# Schematic_MON-14.net
KiCad netlist of a schematic drawn in EAGLE
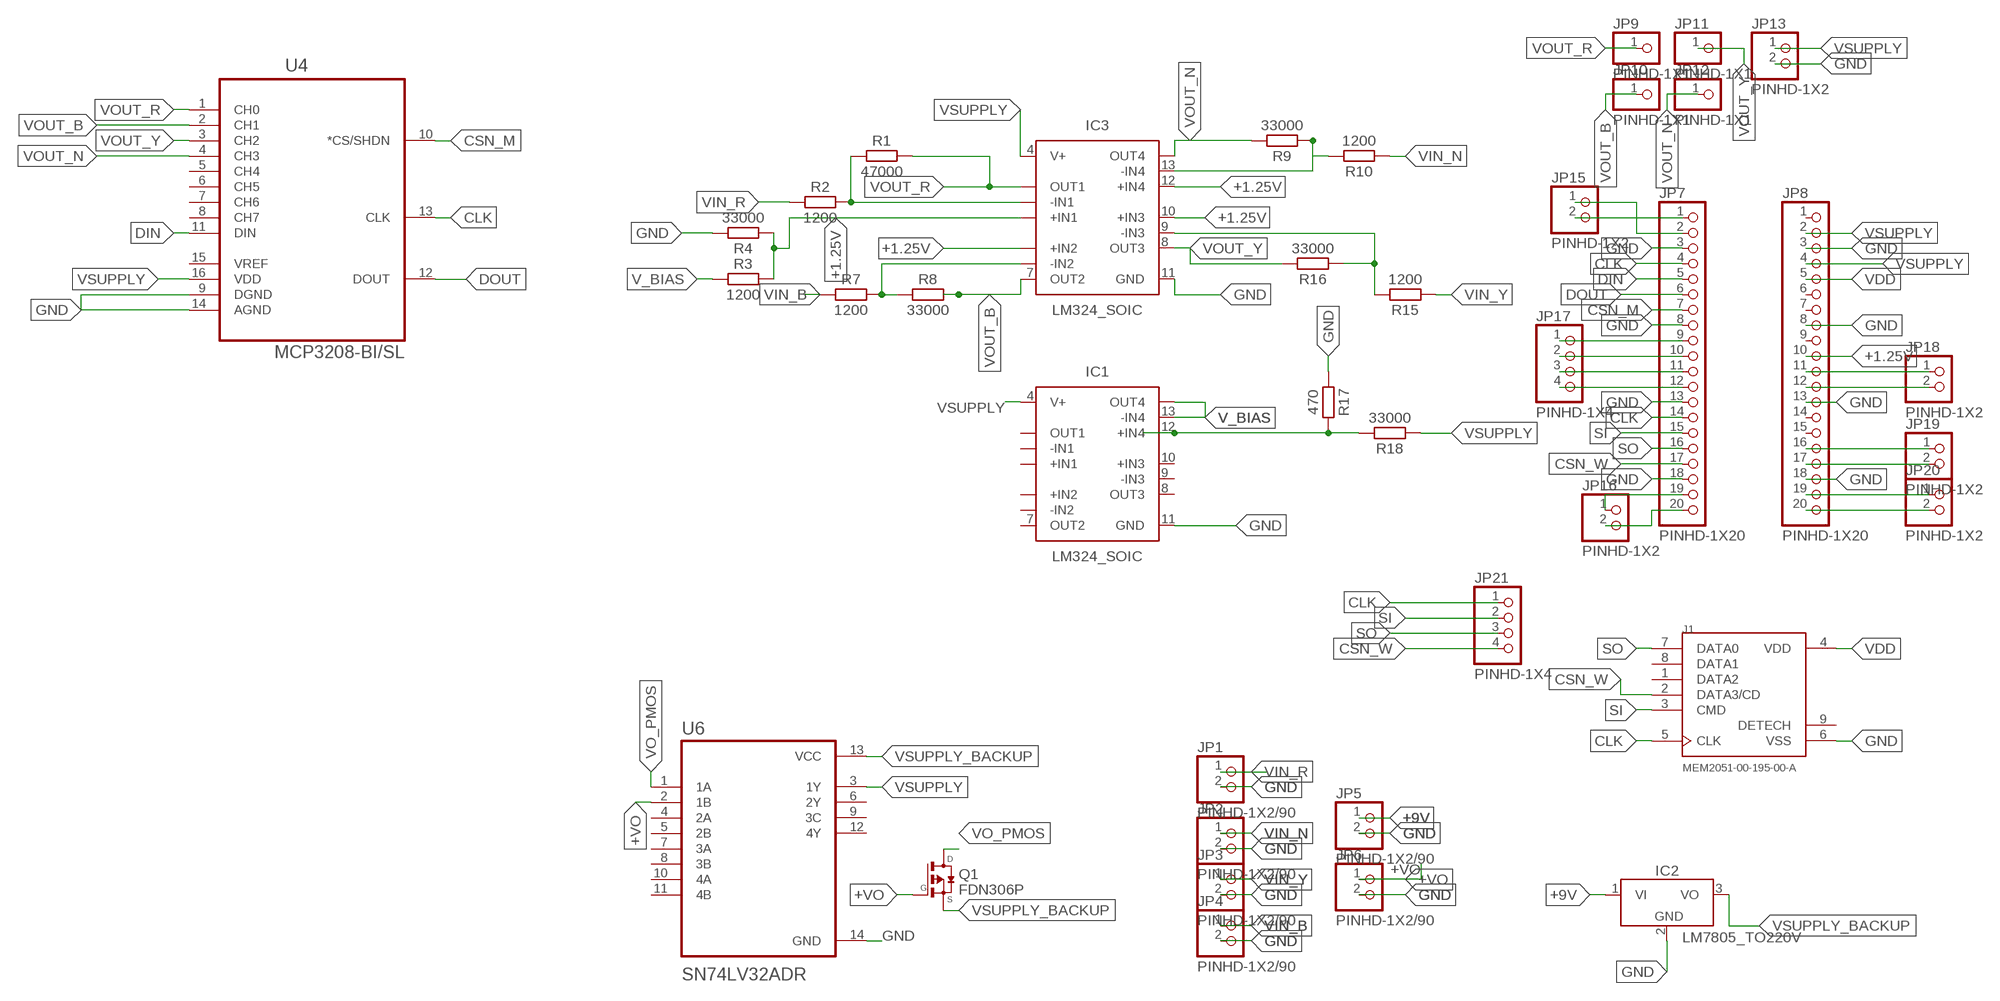
[diagram p0: schematic, sheet 1]

(export (version "E")
  (design (tool "Eeschema 10.0.6"))
  (components
    (comp (ref "IC1")
      (value "LM324_SOIC")
      (footprint "eagle-import:SOIC127P600X175-14N")
      (fields (field (name "MANUFACTURER") "Generic"))
      (libsource (lib "eagle-import") (part "LM324_SOIC"))
    )
    (comp (ref "IC2")
      (value "LM7805_TO220V")
      (footprint "eagle-import:TO220V")
      (fields (field (name "MANUFACTURER") "Generic"))
      (libsource (lib "eagle-import") (part "LM7805_TO220V"))
    )
    (comp (ref "IC3")
      (value "LM324_SOIC")
      (footprint "eagle-import:SOIC127P600X175-14N")
      (fields (field (name "MANUFACTURER") "Generic"))
      (libsource (lib "eagle-import") (part "LM324_SOIC"))
    )
    (comp (ref "J1")
      (value "MEM2051-00-195-00-A")
      (footprint "eagle-import:GCT_MEM2051-00-195-00-A")
      (fields (field (name "MANUFACTURER") "GCT"))
      (libsource (lib "eagle-import") (part "MEM2051-00-195-00-A"))
    )
    (comp (ref "JP1")
      (value "PINHD-1X2/90")
      (footprint "eagle-import:1X02_90")
      (libsource (lib "eagle-import") (part "PINHD-1X2/90"))
    )
    (comp (ref "JP2")
      (value "PINHD-1X2/90")
      (footprint "eagle-import:1X02_90")
      (libsource (lib "eagle-import") (part "PINHD-1X2/90"))
    )
    (comp (ref "JP3")
      (value "PINHD-1X2/90")
      (footprint "eagle-import:1X02_90")
      (libsource (lib "eagle-import") (part "PINHD-1X2/90"))
    )
    (comp (ref "JP4")
      (value "PINHD-1X2/90")
      (footprint "eagle-import:1X02_90")
      (libsource (lib "eagle-import") (part "PINHD-1X2/90"))
    )
    (comp (ref "JP5")
      (value "PINHD-1X2/90")
      (footprint "eagle-import:1X02_90")
      (libsource (lib "eagle-import") (part "PINHD-1X2/90"))
    )
    (comp (ref "JP6")
      (value "PINHD-1X2/90")
      (footprint "eagle-import:1X02_90")
      (libsource (lib "eagle-import") (part "PINHD-1X2/90"))
    )
    (comp (ref "JP7")
      (value "PINHD-1X20")
      (footprint "eagle-import:1X20")
      (libsource (lib "eagle-import") (part "PINHD-1X20"))
    )
    (comp (ref "JP8")
      (value "PINHD-1X20")
      (footprint "eagle-import:1X20")
      (libsource (lib "eagle-import") (part "PINHD-1X20"))
    )
    (comp (ref "JP9")
      (value "PINHD-1X1")
      (footprint "eagle-import:1X01")
      (libsource (lib "eagle-import") (part "PINHD-1X1"))
    )
    (comp (ref "JP10")
      (value "PINHD-1X1")
      (footprint "eagle-import:1X01")
      (libsource (lib "eagle-import") (part "PINHD-1X1"))
    )
    (comp (ref "JP11")
      (value "PINHD-1X1")
      (footprint "eagle-import:1X01")
      (libsource (lib "eagle-import") (part "PINHD-1X1"))
    )
    (comp (ref "JP12")
      (value "PINHD-1X1")
      (footprint "eagle-import:1X01")
      (libsource (lib "eagle-import") (part "PINHD-1X1"))
    )
    (comp (ref "JP13")
      (value "PINHD-1X2")
      (footprint "eagle-import:1X02")
      (libsource (lib "eagle-import") (part "PINHD-1X2"))
    )
    (comp (ref "JP15")
      (value "PINHD-1X2")
      (footprint "eagle-import:1X02")
      (libsource (lib "eagle-import") (part "PINHD-1X2"))
    )
    (comp (ref "JP16")
      (value "PINHD-1X2")
      (footprint "eagle-import:1X02")
      (libsource (lib "eagle-import") (part "PINHD-1X2"))
    )
    (comp (ref "JP17")
      (value "PINHD-1X4")
      (footprint "eagle-import:1X04")
      (libsource (lib "eagle-import") (part "PINHD-1X4"))
    )
    (comp (ref "JP18")
      (value "PINHD-1X2")
      (footprint "eagle-import:1X02")
      (libsource (lib "eagle-import") (part "PINHD-1X2"))
    )
    (comp (ref "JP19")
      (value "PINHD-1X2")
      (footprint "eagle-import:1X02")
      (libsource (lib "eagle-import") (part "PINHD-1X2"))
    )
    (comp (ref "JP20")
      (value "PINHD-1X2")
      (footprint "eagle-import:1X02")
      (libsource (lib "eagle-import") (part "PINHD-1X2"))
    )
    (comp (ref "JP21")
      (value "PINHD-1X4")
      (footprint "eagle-import:1X04")
      (libsource (lib "eagle-import") (part "PINHD-1X4"))
    )
    (comp (ref "Q1")
      (value "FDN306P")
      (footprint "eagle-import:SSOT-3")
      (libsource (lib "eagle-import") (part "FDN306P"))
    )
    (comp (ref "R1")
      (value "47000")
      (footprint "eagle-import:RESC3216X70")
      (libsource (lib "eagle-import") (part "RCHIP-1206(3216-METRIC)_"))
    )
    (comp (ref "R2")
      (value "1200")
      (footprint "eagle-import:RESC3216X70")
      (libsource (lib "eagle-import") (part "RCHIP-1206(3216-METRIC)_"))
    )
    (comp (ref "R3")
      (value "1200")
      (footprint "eagle-import:RESC3216X70")
      (libsource (lib "eagle-import") (part "RCHIP-1206(3216-METRIC)_"))
    )
    (comp (ref "R4")
      (value "33000")
      (footprint "eagle-import:RESC3216X70")
      (libsource (lib "eagle-import") (part "RCHIP-1206(3216-METRIC)_"))
    )
    (comp (ref "R7")
      (value "1200")
      (footprint "eagle-import:RESC3216X70")
      (libsource (lib "eagle-import") (part "RCHIP-1206(3216-METRIC)_"))
    )
    (comp (ref "R8")
      (value "33000")
      (footprint "eagle-import:RESC3216X70")
      (libsource (lib "eagle-import") (part "RCHIP-1206(3216-METRIC)_"))
    )
    (comp (ref "R9")
      (value "33000")
      (footprint "eagle-import:RESC3216X70")
      (libsource (lib "eagle-import") (part "RCHIP-1206(3216-METRIC)_"))
    )
    (comp (ref "R10")
      (value "1200")
      (footprint "eagle-import:RESC3216X70")
      (libsource (lib "eagle-import") (part "RCHIP-1206(3216-METRIC)_"))
    )
    (comp (ref "R15")
      (value "1200")
      (footprint "eagle-import:RESC3216X70")
      (libsource (lib "eagle-import") (part "RCHIP-1206(3216-METRIC)_"))
    )
    (comp (ref "R16")
      (value "33000")
      (footprint "eagle-import:RESC3216X70")
      (libsource (lib "eagle-import") (part "RCHIP-1206(3216-METRIC)_"))
    )
    (comp (ref "R17")
      (value "470")
      (footprint "eagle-import:RESC3216X70")
      (libsource (lib "eagle-import") (part "RCHIP-1206(3216-METRIC)_"))
    )
    (comp (ref "R18")
      (value "33000")
      (footprint "eagle-import:RESC3216X70")
      (libsource (lib "eagle-import") (part "RCHIP-1206(3216-METRIC)_"))
    )
    (comp (ref "U4")
      (value "MCP3208-BI/SL")
      (footprint "eagle-import:SOIC127P600X175-16N")
      (libsource (lib "eagle-import") (part "MCP3208-BI/SL"))
    )
    (comp (ref "U6")
      (value "SN74LV32ADR")
      (footprint "eagle-import:SOIC127P600X175-14N")
      (fields (field (name "MANUFACTURER") "Texas Instruments"))
      (libsource (lib "eagle-import") (part "SN74LV32ADR"))
    )
  )
  (nets
    (net (code "1") (name "+1.25V") (class "Default")
      (node (ref "IC3") (pin "10") (pinfunction "+IN3_10") (pintype "passive"))
      (node (ref "IC3") (pin "12") (pinfunction "+IN4_12") (pintype "bidirectional"))
      (node (ref "IC3") (pin "3") (pinfunction "+IN1_3") (pintype "bidirectional"))
      (node (ref "IC3") (pin "5") (pinfunction "+IN2_5") (pintype "passive"))
      (node (ref "JP8") (pin "10") (pinfunction "10_10") (pintype "passive"))
      (node (ref "R3") (pin "2") (pinfunction "2_2") (pintype "passive"))
      (node (ref "R4") (pin "1") (pinfunction "1_1") (pintype "passive"))
    )
    (net (code "2") (name "+9V") (class "Default")
      (node (ref "IC2") (pin "1") (pinfunction "VI_1") (pintype "input"))
      (node (ref "JP5") (pin "1") (pinfunction "1_1") (pintype "passive"))
    )
    (net (code "3") (name "+VO") (class "Default")
      (node (ref "JP6") (pin "1") (pinfunction "1_1") (pintype "passive"))
      (node (ref "Q1") (pin "1") (pinfunction "G_1") (pintype "passive"))
      (node (ref "U6") (pin "2") (pinfunction "1B_2") (pintype "input"))
    )
    (net (code "4") (name "CLK") (class "Default")
      (node (ref "J1") (pin "5") (pinfunction "CLK_5") (pintype "bidirectional"))
      (node (ref "JP21") (pin "1") (pinfunction "1_1") (pintype "passive"))
      (node (ref "JP7") (pin "14") (pinfunction "14_14") (pintype "passive"))
      (node (ref "JP7") (pin "4") (pinfunction "4_4") (pintype "passive"))
      (node (ref "U4") (pin "13") (pinfunction "CLK_13") (pintype "input"))
    )
    (net (code "5") (name "CSN_M") (class "Default")
      (node (ref "JP7") (pin "7") (pinfunction "7_7") (pintype "passive"))
      (node (ref "U4") (pin "10") (pinfunction "*CS/SHDN_10") (pintype "input"))
    )
    (net (code "6") (name "CSN_W") (class "Default")
      (node (ref "J1") (pin "2") (pinfunction "DATA3/CD_2") (pintype "bidirectional"))
      (node (ref "JP21") (pin "4") (pinfunction "4_4") (pintype "passive"))
      (node (ref "JP7") (pin "17") (pinfunction "17_17") (pintype "passive"))
    )
    (net (code "7") (name "DIN") (class "Default")
      (node (ref "JP7") (pin "5") (pinfunction "5_5") (pintype "passive"))
      (node (ref "U4") (pin "11") (pinfunction "DIN_11") (pintype "input"))
    )
    (net (code "8") (name "DOUT") (class "Default")
      (node (ref "JP7") (pin "6") (pinfunction "6_6") (pintype "passive"))
      (node (ref "U4") (pin "12") (pinfunction "DOUT_12") (pintype "output"))
    )
    (net (code "9") (name "GND") (class "Default")
      (node (ref "IC1") (pin "11") (pinfunction "GND_11") (pintype "passive"))
      (node (ref "IC2") (pin "2") (pinfunction "GND_2") (pintype "passive"))
      (node (ref "IC3") (pin "11") (pinfunction "GND_11") (pintype "passive"))
      (node (ref "J1") (pin "6") (pinfunction "VSS_6") (pintype "power_in"))
      (node (ref "JP1") (pin "2") (pinfunction "2_2") (pintype "passive"))
      (node (ref "JP13") (pin "2") (pinfunction "2_2") (pintype "passive"))
      (node (ref "JP2") (pin "2") (pinfunction "2_2") (pintype "passive"))
      (node (ref "JP3") (pin "2") (pinfunction "2_2") (pintype "passive"))
      (node (ref "JP4") (pin "2") (pinfunction "2_2") (pintype "passive"))
      (node (ref "JP5") (pin "2") (pinfunction "2_2") (pintype "passive"))
      (node (ref "JP6") (pin "2") (pinfunction "2_2") (pintype "passive"))
      (node (ref "JP7") (pin "13") (pinfunction "13_13") (pintype "passive"))
      (node (ref "JP7") (pin "18") (pinfunction "18_18") (pintype "passive"))
      (node (ref "JP7") (pin "3") (pinfunction "3_3") (pintype "passive"))
      (node (ref "JP7") (pin "8") (pinfunction "8_8") (pintype "passive"))
      (node (ref "JP8") (pin "13") (pinfunction "13_13") (pintype "passive"))
      (node (ref "JP8") (pin "18") (pinfunction "18_18") (pintype "passive"))
      (node (ref "JP8") (pin "3") (pinfunction "3_3") (pintype "passive"))
      (node (ref "JP8") (pin "8") (pinfunction "8_8") (pintype "passive"))
      (node (ref "R17") (pin "1") (pinfunction "1_1") (pintype "passive"))
      (node (ref "R4") (pin "2") (pinfunction "2_2") (pintype "passive"))
      (node (ref "U4") (pin "14") (pinfunction "AGND_14") (pintype "passive"))
      (node (ref "U4") (pin "9") (pinfunction "DGND_9") (pintype "passive"))
      (node (ref "U6") (pin "14") (pinfunction "GND_14") (pintype "power_in"))
    )
    (net (code "10") (name "Net-(IC1-+IN4)") (class "Default")
      (node (ref "IC1") (pin "12") (pinfunction "+IN4_12") (pintype "bidirectional"))
      (node (ref "R17") (pin "2") (pinfunction "2_2") (pintype "passive"))
      (node (ref "R18") (pin "2") (pinfunction "2_2") (pintype "passive"))
    )
    (net (code "11") (name "Net-(IC3--IN1)") (class "Default")
      (node (ref "IC3") (pin "2") (pinfunction "-IN1_2") (pintype "input"))
      (node (ref "R1") (pin "1") (pinfunction "1_1") (pintype "passive"))
      (node (ref "R2") (pin "2") (pinfunction "2_2") (pintype "passive"))
    )
    (net (code "12") (name "Net-(IC3--IN2)") (class "Default")
      (node (ref "IC3") (pin "6") (pinfunction "-IN2_6") (pintype "passive"))
      (node (ref "R7") (pin "2") (pinfunction "2_2") (pintype "passive"))
      (node (ref "R8") (pin "1") (pinfunction "1_1") (pintype "passive"))
    )
    (net (code "13") (name "Net-(IC3--IN3)") (class "Default")
      (node (ref "IC3") (pin "9") (pinfunction "-IN3_9") (pintype "passive"))
      (node (ref "R15") (pin "2") (pinfunction "2_2") (pintype "passive"))
      (node (ref "R16") (pin "1") (pinfunction "1_1") (pintype "passive"))
    )
    (net (code "14") (name "Net-(IC3--IN4)") (class "Default")
      (node (ref "IC3") (pin "13") (pinfunction "-IN4_13") (pintype "bidirectional"))
      (node (ref "R10") (pin "2") (pinfunction "2_2") (pintype "passive"))
      (node (ref "R9") (pin "1") (pinfunction "1_1") (pintype "passive"))
    )
    (net (code "15") (name "Net-(JP15-Pad1)") (class "Default")
      (node (ref "JP15") (pin "1") (pinfunction "1_1") (pintype "passive"))
      (node (ref "JP7") (pin "2") (pinfunction "2_2") (pintype "passive"))
    )
    (net (code "16") (name "Net-(JP15-Pad2)") (class "Default")
      (node (ref "JP15") (pin "2") (pinfunction "2_2") (pintype "passive"))
      (node (ref "JP7") (pin "1") (pinfunction "1_1") (pintype "passive"))
    )
    (net (code "17") (name "Net-(JP16-Pad1)") (class "Default")
      (node (ref "JP16") (pin "1") (pinfunction "1_1") (pintype "passive"))
      (node (ref "JP7") (pin "19") (pinfunction "19_19") (pintype "passive"))
    )
    (net (code "18") (name "Net-(JP16-Pad2)") (class "Default")
      (node (ref "JP16") (pin "2") (pinfunction "2_2") (pintype "passive"))
      (node (ref "JP7") (pin "20") (pinfunction "20_20") (pintype "passive"))
    )
    (net (code "19") (name "Net-(JP17-Pad1)") (class "Default")
      (node (ref "JP17") (pin "1") (pinfunction "1_1") (pintype "passive"))
      (node (ref "JP7") (pin "9") (pinfunction "9_9") (pintype "passive"))
    )
    (net (code "20") (name "Net-(JP17-Pad2)") (class "Default")
      (node (ref "JP17") (pin "2") (pinfunction "2_2") (pintype "passive"))
      (node (ref "JP7") (pin "10") (pinfunction "10_10") (pintype "passive"))
    )
    (net (code "21") (name "Net-(JP17-Pad3)") (class "Default")
      (node (ref "JP17") (pin "3") (pinfunction "3_3") (pintype "passive"))
      (node (ref "JP7") (pin "11") (pinfunction "11_11") (pintype "passive"))
    )
    (net (code "22") (name "Net-(JP17-Pad4)") (class "Default")
      (node (ref "JP17") (pin "4") (pinfunction "4_4") (pintype "passive"))
      (node (ref "JP7") (pin "12") (pinfunction "12_12") (pintype "passive"))
    )
    (net (code "23") (name "Net-(JP18-Pad1)") (class "Default")
      (node (ref "JP18") (pin "1") (pinfunction "1_1") (pintype "passive"))
      (node (ref "JP8") (pin "11") (pinfunction "11_11") (pintype "passive"))
    )
    (net (code "24") (name "Net-(JP18-Pad2)") (class "Default")
      (node (ref "JP18") (pin "2") (pinfunction "2_2") (pintype "passive"))
      (node (ref "JP8") (pin "12") (pinfunction "12_12") (pintype "passive"))
    )
    (net (code "25") (name "Net-(JP19-Pad1)") (class "Default")
      (node (ref "JP19") (pin "1") (pinfunction "1_1") (pintype "passive"))
      (node (ref "JP8") (pin "16") (pinfunction "16_16") (pintype "passive"))
    )
    (net (code "26") (name "Net-(JP19-Pad2)") (class "Default")
      (node (ref "JP19") (pin "2") (pinfunction "2_2") (pintype "passive"))
      (node (ref "JP8") (pin "17") (pinfunction "17_17") (pintype "passive"))
    )
    (net (code "27") (name "Net-(JP20-Pad1)") (class "Default")
      (node (ref "JP20") (pin "1") (pinfunction "1_1") (pintype "passive"))
      (node (ref "JP8") (pin "19") (pinfunction "19_19") (pintype "passive"))
    )
    (net (code "28") (name "Net-(JP20-Pad2)") (class "Default")
      (node (ref "JP20") (pin "2") (pinfunction "2_2") (pintype "passive"))
      (node (ref "JP8") (pin "20") (pinfunction "20_20") (pintype "passive"))
    )
    (net (code "29") (name "SI") (class "Default")
      (node (ref "J1") (pin "3") (pinfunction "CMD_3") (pintype "bidirectional"))
      (node (ref "JP21") (pin "2") (pinfunction "2_2") (pintype "passive"))
      (node (ref "JP7") (pin "15") (pinfunction "15_15") (pintype "passive"))
    )
    (net (code "30") (name "SO") (class "Default")
      (node (ref "J1") (pin "7") (pinfunction "DATA0_7") (pintype "bidirectional"))
      (node (ref "JP21") (pin "3") (pinfunction "3_3") (pintype "passive"))
      (node (ref "JP7") (pin "16") (pinfunction "16_16") (pintype "passive"))
    )
    (net (code "31") (name "VDD") (class "Default")
      (node (ref "J1") (pin "4") (pinfunction "VDD_4") (pintype "power_in"))
      (node (ref "JP8") (pin "5") (pinfunction "5_5") (pintype "passive"))
    )
    (net (code "32") (name "VIN_B") (class "Default")
      (node (ref "JP4") (pin "1") (pinfunction "1_1") (pintype "passive"))
      (node (ref "R7") (pin "1") (pinfunction "1_1") (pintype "passive"))
    )
    (net (code "33") (name "VIN_N") (class "Default")
      (node (ref "JP2") (pin "1") (pinfunction "1_1") (pintype "passive"))
      (node (ref "R10") (pin "1") (pinfunction "1_1") (pintype "passive"))
    )
    (net (code "34") (name "VIN_R") (class "Default")
      (node (ref "JP1") (pin "1") (pinfunction "1_1") (pintype "passive"))
      (node (ref "R2") (pin "1") (pinfunction "1_1") (pintype "passive"))
    )
    (net (code "35") (name "VIN_Y") (class "Default")
      (node (ref "JP3") (pin "1") (pinfunction "1_1") (pintype "passive"))
      (node (ref "R15") (pin "1") (pinfunction "1_1") (pintype "passive"))
    )
    (net (code "36") (name "VOUT_B") (class "Default")
      (node (ref "IC3") (pin "7") (pinfunction "OUT2_7") (pintype "passive"))
      (node (ref "JP10") (pin "1") (pinfunction "1_1") (pintype "passive"))
      (node (ref "R8") (pin "2") (pinfunction "2_2") (pintype "passive"))
      (node (ref "U4") (pin "2") (pinfunction "CH1_2") (pintype "input"))
    )
    (net (code "37") (name "VOUT_N") (class "Default")
      (node (ref "IC3") (pin "14") (pinfunction "OUT4_14") (pintype "output"))
      (node (ref "JP12") (pin "1") (pinfunction "1_1") (pintype "passive"))
      (node (ref "R9") (pin "2") (pinfunction "2_2") (pintype "passive"))
      (node (ref "U4") (pin "4") (pinfunction "CH3_4") (pintype "input"))
    )
    (net (code "38") (name "VOUT_R") (class "Default")
      (node (ref "IC3") (pin "1") (pinfunction "OUT1_1") (pintype "input"))
      (node (ref "JP9") (pin "1") (pinfunction "1_1") (pintype "passive"))
      (node (ref "R1") (pin "2") (pinfunction "2_2") (pintype "passive"))
      (node (ref "U4") (pin "1") (pinfunction "CH0_1") (pintype "input"))
    )
    (net (code "39") (name "VOUT_Y") (class "Default")
      (node (ref "IC3") (pin "8") (pinfunction "OUT3_8") (pintype "passive"))
      (node (ref "JP11") (pin "1") (pinfunction "1_1") (pintype "passive"))
      (node (ref "R16") (pin "2") (pinfunction "2_2") (pintype "passive"))
      (node (ref "U4") (pin "3") (pinfunction "CH2_3") (pintype "input"))
    )
    (net (code "40") (name "VO_PMOS") (class "Default")
      (node (ref "Q1") (pin "3") (pinfunction "D_3") (pintype "passive"))
      (node (ref "U6") (pin "1") (pinfunction "1A_1") (pintype "input"))
    )
    (net (code "41") (name "VSUPPLY") (class "Default")
      (node (ref "IC1") (pin "4") (pinfunction "V+_4") (pintype "passive"))
      (node (ref "IC3") (pin "4") (pinfunction "V+_4") (pintype "passive"))
      (node (ref "JP13") (pin "1") (pinfunction "1_1") (pintype "passive"))
      (node (ref "JP8") (pin "2") (pinfunction "2_2") (pintype "passive"))
      (node (ref "JP8") (pin "4") (pinfunction "4_4") (pintype "passive"))
      (node (ref "R18") (pin "1") (pinfunction "1_1") (pintype "passive"))
      (node (ref "U4") (pin "16") (pinfunction "VDD_16") (pintype "power_in"))
      (node (ref "U6") (pin "3") (pinfunction "1Y_3") (pintype "output"))
    )
    (net (code "42") (name "VSUPPLY_BACKUP") (class "Default")
      (node (ref "IC2") (pin "3") (pinfunction "VO_3") (pintype "output"))
      (node (ref "Q1") (pin "2") (pinfunction "S_2") (pintype "passive"))
      (node (ref "U6") (pin "13") (pinfunction "VCC_13") (pintype "power_in"))
    )
    (net (code "43") (name "V_BIAS") (class "Default")
      (node (ref "IC1") (pin "13") (pinfunction "-IN4_13") (pintype "bidirectional"))
      (node (ref "IC1") (pin "14") (pinfunction "OUT4_14") (pintype "output"))
      (node (ref "R3") (pin "1") (pinfunction "1_1") (pintype "passive"))
    )
    (net (code "44") (name "unconnected-(IC1-+IN1-Pad3)") (class "Default")
      (node (ref "IC1") (pin "3") (pinfunction "+IN1_3") (pintype "bidirectional"))
    )
    (net (code "45") (name "unconnected-(IC1-+IN2-Pad5)") (class "Default")
      (node (ref "IC1") (pin "5") (pinfunction "+IN2_5") (pintype "passive"))
    )
    (net (code "46") (name "unconnected-(IC1-+IN3-Pad10)") (class "Default")
      (node (ref "IC1") (pin "10") (pinfunction "+IN3_10") (pintype "passive"))
    )
    (net (code "47") (name "unconnected-(IC1--IN1-Pad2)") (class "Default")
      (node (ref "IC1") (pin "2") (pinfunction "-IN1_2") (pintype "input"))
    )
    (net (code "48") (name "unconnected-(IC1--IN2-Pad6)") (class "Default")
      (node (ref "IC1") (pin "6") (pinfunction "-IN2_6") (pintype "passive"))
    )
    (net (code "49") (name "unconnected-(IC1--IN3-Pad9)") (class "Default")
      (node (ref "IC1") (pin "9") (pinfunction "-IN3_9") (pintype "passive"))
    )
    (net (code "50") (name "unconnected-(IC1-OUT1-Pad1)") (class "Default")
      (node (ref "IC1") (pin "1") (pinfunction "OUT1_1") (pintype "input"))
    )
    (net (code "51") (name "unconnected-(IC1-OUT2-Pad7)") (class "Default")
      (node (ref "IC1") (pin "7") (pinfunction "OUT2_7") (pintype "passive"))
    )
    (net (code "52") (name "unconnected-(IC1-OUT3-Pad8)") (class "Default")
      (node (ref "IC1") (pin "8") (pinfunction "OUT3_8") (pintype "passive"))
    )
    (net (code "53") (name "unconnected-(J1-DATA1-Pad8)") (class "Default")
      (node (ref "J1") (pin "8") (pinfunction "DATA1_8") (pintype "bidirectional"))
    )
    (net (code "54") (name "unconnected-(J1-DATA2-Pad1)") (class "Default")
      (node (ref "J1") (pin "1") (pinfunction "DATA2_1") (pintype "bidirectional"))
    )
    (net (code "55") (name "unconnected-(J1-DETECH-Pad9)") (class "Default")
      (node (ref "J1") (pin "9") (pinfunction "DETECH_9") (pintype "passive"))
    )
    (net (code "56") (name "unconnected-(JP8-Pad1)") (class "Default")
      (node (ref "JP8") (pin "1") (pinfunction "1_1") (pintype "passive"))
    )
    (net (code "57") (name "unconnected-(JP8-Pad6)") (class "Default")
      (node (ref "JP8") (pin "6") (pinfunction "6_6") (pintype "passive"))
    )
    (net (code "58") (name "unconnected-(JP8-Pad7)") (class "Default")
      (node (ref "JP8") (pin "7") (pinfunction "7_7") (pintype "passive"))
    )
    (net (code "59") (name "unconnected-(JP8-Pad9)") (class "Default")
      (node (ref "JP8") (pin "9") (pinfunction "9_9") (pintype "passive"))
    )
    (net (code "60") (name "unconnected-(JP8-Pad14)") (class "Default")
      (node (ref "JP8") (pin "14") (pinfunction "14_14") (pintype "passive"))
    )
    (net (code "61") (name "unconnected-(JP8-Pad15)") (class "Default")
      (node (ref "JP8") (pin "15") (pinfunction "15_15") (pintype "passive"))
    )
    (net (code "62") (name "unconnected-(U4-CH4-Pad5)") (class "Default")
      (node (ref "U4") (pin "5") (pinfunction "CH4_5") (pintype "input"))
    )
    (net (code "63") (name "unconnected-(U4-CH5-Pad6)") (class "Default")
      (node (ref "U4") (pin "6") (pinfunction "CH5_6") (pintype "input"))
    )
    (net (code "64") (name "unconnected-(U4-CH6-Pad7)") (class "Default")
      (node (ref "U4") (pin "7") (pinfunction "CH6_7") (pintype "input"))
    )
    (net (code "65") (name "unconnected-(U4-CH7-Pad8)") (class "Default")
      (node (ref "U4") (pin "8") (pinfunction "CH7_8") (pintype "input"))
    )
    (net (code "66") (name "unconnected-(U4-VREF-Pad15)") (class "Default")
      (node (ref "U4") (pin "15") (pinfunction "VREF_15") (pintype "input"))
    )
    (net (code "67") (name "unconnected-(U6-2A-Pad4)") (class "Default")
      (node (ref "U6") (pin "4") (pinfunction "2A_4") (pintype "input"))
    )
    (net (code "68") (name "unconnected-(U6-2B-Pad5)") (class "Default")
      (node (ref "U6") (pin "5") (pinfunction "2B_5") (pintype "input"))
    )
    (net (code "69") (name "unconnected-(U6-2Y-Pad6)") (class "Default")
      (node (ref "U6") (pin "6") (pinfunction "2Y_6") (pintype "output"))
    )
    (net (code "70") (name "unconnected-(U6-3A-Pad7)") (class "Default")
      (node (ref "U6") (pin "7") (pinfunction "3A_7") (pintype "input"))
    )
    (net (code "71") (name "unconnected-(U6-3B-Pad8)") (class "Default")
      (node (ref "U6") (pin "8") (pinfunction "3B_8") (pintype "input"))
    )
    (net (code "72") (name "unconnected-(U6-3C-Pad9)") (class "Default")
      (node (ref "U6") (pin "9") (pinfunction "3C_9") (pintype "output"))
    )
    (net (code "73") (name "unconnected-(U6-4A-Pad10)") (class "Default")
      (node (ref "U6") (pin "10") (pinfunction "4A_10") (pintype "input"))
    )
    (net (code "74") (name "unconnected-(U6-4B-Pad11)") (class "Default")
      (node (ref "U6") (pin "11") (pinfunction "4B_11") (pintype "input"))
    )
    (net (code "75") (name "unconnected-(U6-4Y-Pad12)") (class "Default")
      (node (ref "U6") (pin "12") (pinfunction "4Y_12") (pintype "output"))
    )
  )
)
